# Eagle_Power.net
KiCad netlist of a schematic drawn in EAGLE
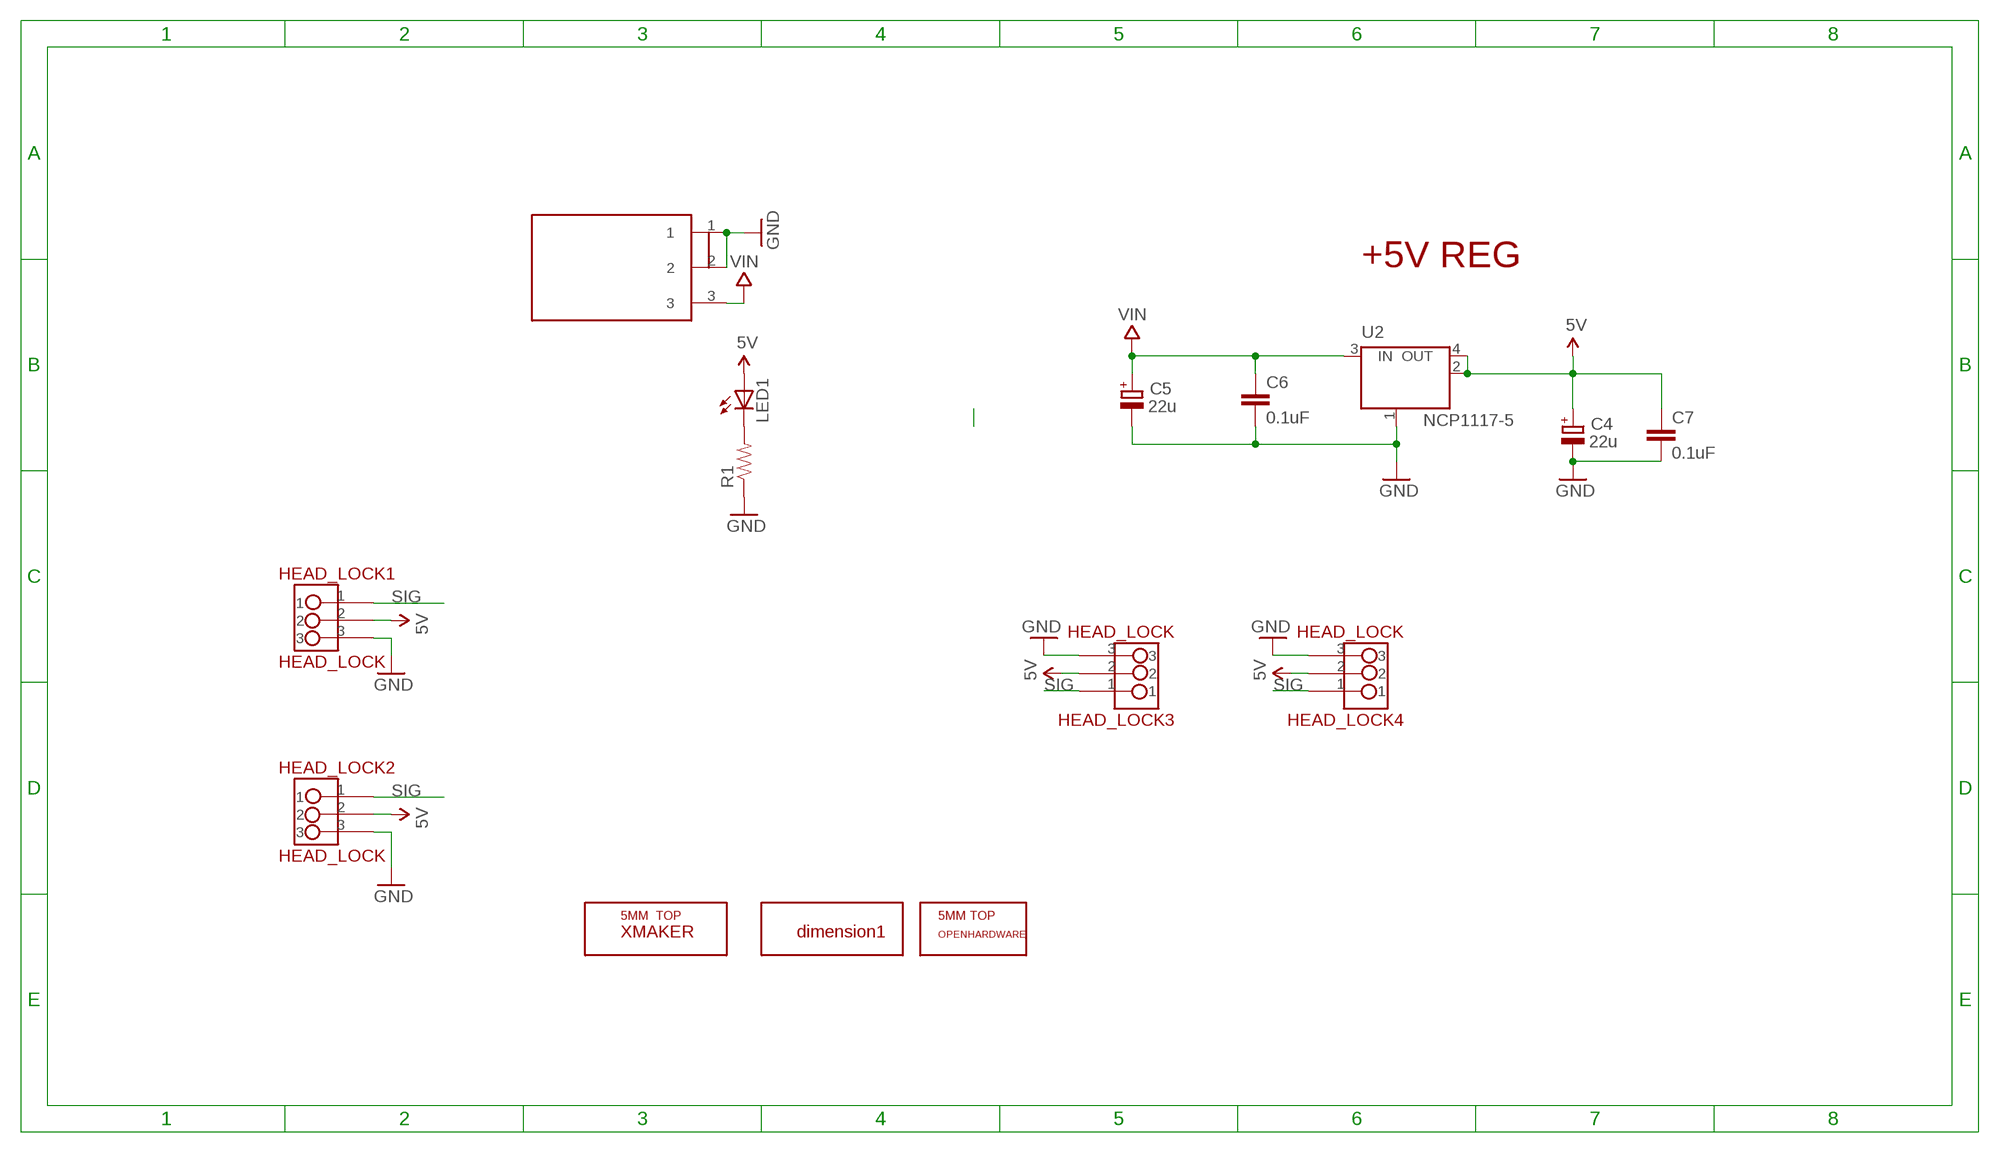
[diagram p0: schematic, sheet 1]

(export (version "E")
  (design (tool "Eeschema 10.0.6"))
  (components
    (comp (ref "C4")
      (value "22u")
      (footprint "eagle-import:SMC_B")
      (libsource (lib "eagle-import") (part "CPOL-EUSMCB"))
    )
    (comp (ref "C5")
      (value "22u")
      (footprint "eagle-import:SMC_B")
      (libsource (lib "eagle-import") (part "CPOL-EUSMCB"))
    )
    (comp (ref "C6")
      (value "0.1uF")
      (footprint "eagle-import:0603-CAP")
      (libsource (lib "eagle-import") (part "0.1UF-25V(+80/-20%)(0603)"))
    )
    (comp (ref "C7")
      (value "0.1uF")
      (footprint "eagle-import:0603-CAP")
      (libsource (lib "eagle-import") (part "0.1UF-25V(+80/-20%)(0603)"))
    )
    (comp (ref "HEAD_LOCK1")
      (value "HEAD_LOCK")
      (footprint "eagle-import:HEAD_LOCK")
      (libsource (lib "eagle-import") (part "HEAD_LOCK"))
    )
    (comp (ref "HEAD_LOCK2")
      (value "HEAD_LOCK")
      (footprint "eagle-import:HEAD_LOCK")
      (libsource (lib "eagle-import") (part "HEAD_LOCK"))
    )
    (comp (ref "HEAD_LOCK3")
      (value "HEAD_LOCK")
      (footprint "eagle-import:HEAD_LOCK")
      (libsource (lib "eagle-import") (part "HEAD_LOCK"))
    )
    (comp (ref "HEAD_LOCK4")
      (value "HEAD_LOCK")
      (footprint "eagle-import:HEAD_LOCK")
      (libsource (lib "eagle-import") (part "HEAD_LOCK"))
    )
    (comp (ref "LED1")
      (value "LEDSML0603")
      (footprint "eagle-import:SML0603")
      (libsource (lib "eagle-import") (part "LEDSML0603"))
    )
    (comp (ref "R1")
      (value "RESISTOR0603-RES")
      (footprint "eagle-import:0603-RES")
      (libsource (lib "eagle-import") (part "RESISTOR0603-RES"))
    )
    (comp (ref "U$2")
      (value "OPENHARDWARE_5MM_TOP")
      (footprint "eagle-import:OPENSOURCE_5MM_TOP")
      (libsource (lib "eagle-import") (part "OPENHARDWARE_5MM_TOP"))
    )
    (comp (ref "U$4")
      (value "DIMENSION1")
      (footprint "eagle-import:DIMENSION1")
      (libsource (lib "eagle-import") (part "DIMENSION1"))
    )
    (comp (ref "U$5")
      (value "DC5.52.1MM")
      (footprint "eagle-import:DC5.5_2.1MM")
      (libsource (lib "eagle-import") (part "DC5.52.1MM"))
    )
    (comp (ref "U$6")
      (value "XMAKERLOGO_5MM_TOP")
      (footprint "eagle-import:XMAKERLOGO_5MM_TOP")
      (libsource (lib "eagle-import") (part "XMAKERLOGO_5MM_TOP"))
    )
    (comp (ref "U2")
      (value "NCP1117-5")
      (footprint "eagle-import:LINEAR_SOT223")
      (libsource (lib "eagle-import") (part "LINEAR_MC33269ST"))
    )
  )
  (nets
    (net (code "1") (name "/SIG") (class "Default")
      (node (ref "HEAD_LOCK1") (pin "1") (pinfunction "1_1") (pintype "passive"))
      (node (ref "HEAD_LOCK2") (pin "1") (pinfunction "1_1") (pintype "passive"))
      (node (ref "HEAD_LOCK3") (pin "1") (pinfunction "1_1") (pintype "passive"))
      (node (ref "HEAD_LOCK4") (pin "1") (pinfunction "1_1") (pintype "passive"))
    )
    (net (code "2") (name "5V") (class "Default")
      (node (ref "C4") (pin "+") (pinfunction "+_+") (pintype "passive"))
      (node (ref "C7") (pin "1") (pinfunction "1_1") (pintype "passive"))
      (node (ref "HEAD_LOCK1") (pin "2") (pinfunction "2_2") (pintype "passive"))
      (node (ref "HEAD_LOCK2") (pin "2") (pinfunction "2_2") (pintype "passive"))
      (node (ref "HEAD_LOCK3") (pin "2") (pinfunction "2_2") (pintype "passive"))
      (node (ref "HEAD_LOCK4") (pin "2") (pinfunction "2_2") (pintype "passive"))
      (node (ref "LED1") (pin "A") (pinfunction "A_A") (pintype "passive"))
      (node (ref "U2") (pin "2") (pinfunction "OUT_2") (pintype "passive"))
      (node (ref "U2") (pin "4") (pinfunction "OUT_4") (pintype "passive"))
    )
    (net (code "3") (name "GND") (class "Default")
      (node (ref "C4") (pin "-") (pinfunction "-_-") (pintype "passive"))
      (node (ref "C5") (pin "-") (pinfunction "-_-") (pintype "passive"))
      (node (ref "C6") (pin "2") (pinfunction "2_2") (pintype "passive"))
      (node (ref "C7") (pin "2") (pinfunction "2_2") (pintype "passive"))
      (node (ref "HEAD_LOCK1") (pin "3") (pinfunction "3_3") (pintype "passive"))
      (node (ref "HEAD_LOCK2") (pin "3") (pinfunction "3_3") (pintype "passive"))
      (node (ref "HEAD_LOCK3") (pin "3") (pinfunction "3_3") (pintype "passive"))
      (node (ref "HEAD_LOCK4") (pin "3") (pinfunction "3_3") (pintype "passive"))
      (node (ref "R1") (pin "1") (pinfunction "1_1") (pintype "passive"))
      (node (ref "U$5") (pin "1") (pinfunction "1_1") (pintype "bidirectional"))
      (node (ref "U$5") (pin "2") (pinfunction "2_2") (pintype "bidirectional"))
      (node (ref "U2") (pin "1") (pinfunction "GND/ADJ_1") (pintype "input"))
    )
    (net (code "4") (name "Net-(LED1-PadC)") (class "Default")
      (node (ref "LED1") (pin "C") (pinfunction "C_C") (pintype "passive"))
      (node (ref "R1") (pin "2") (pinfunction "2_2") (pintype "passive"))
    )
    (net (code "5") (name "VIN") (class "Default")
      (node (ref "C5") (pin "+") (pinfunction "+_+") (pintype "passive"))
      (node (ref "C6") (pin "1") (pinfunction "1_1") (pintype "passive"))
      (node (ref "U$5") (pin "3") (pinfunction "3_3") (pintype "bidirectional"))
      (node (ref "U2") (pin "3") (pinfunction "IN_3") (pintype "input"))
    )
  )
)
